# CAN_ISO_Sensor_unit.net
KiCad netlist of a schematic drawn in EAGLE
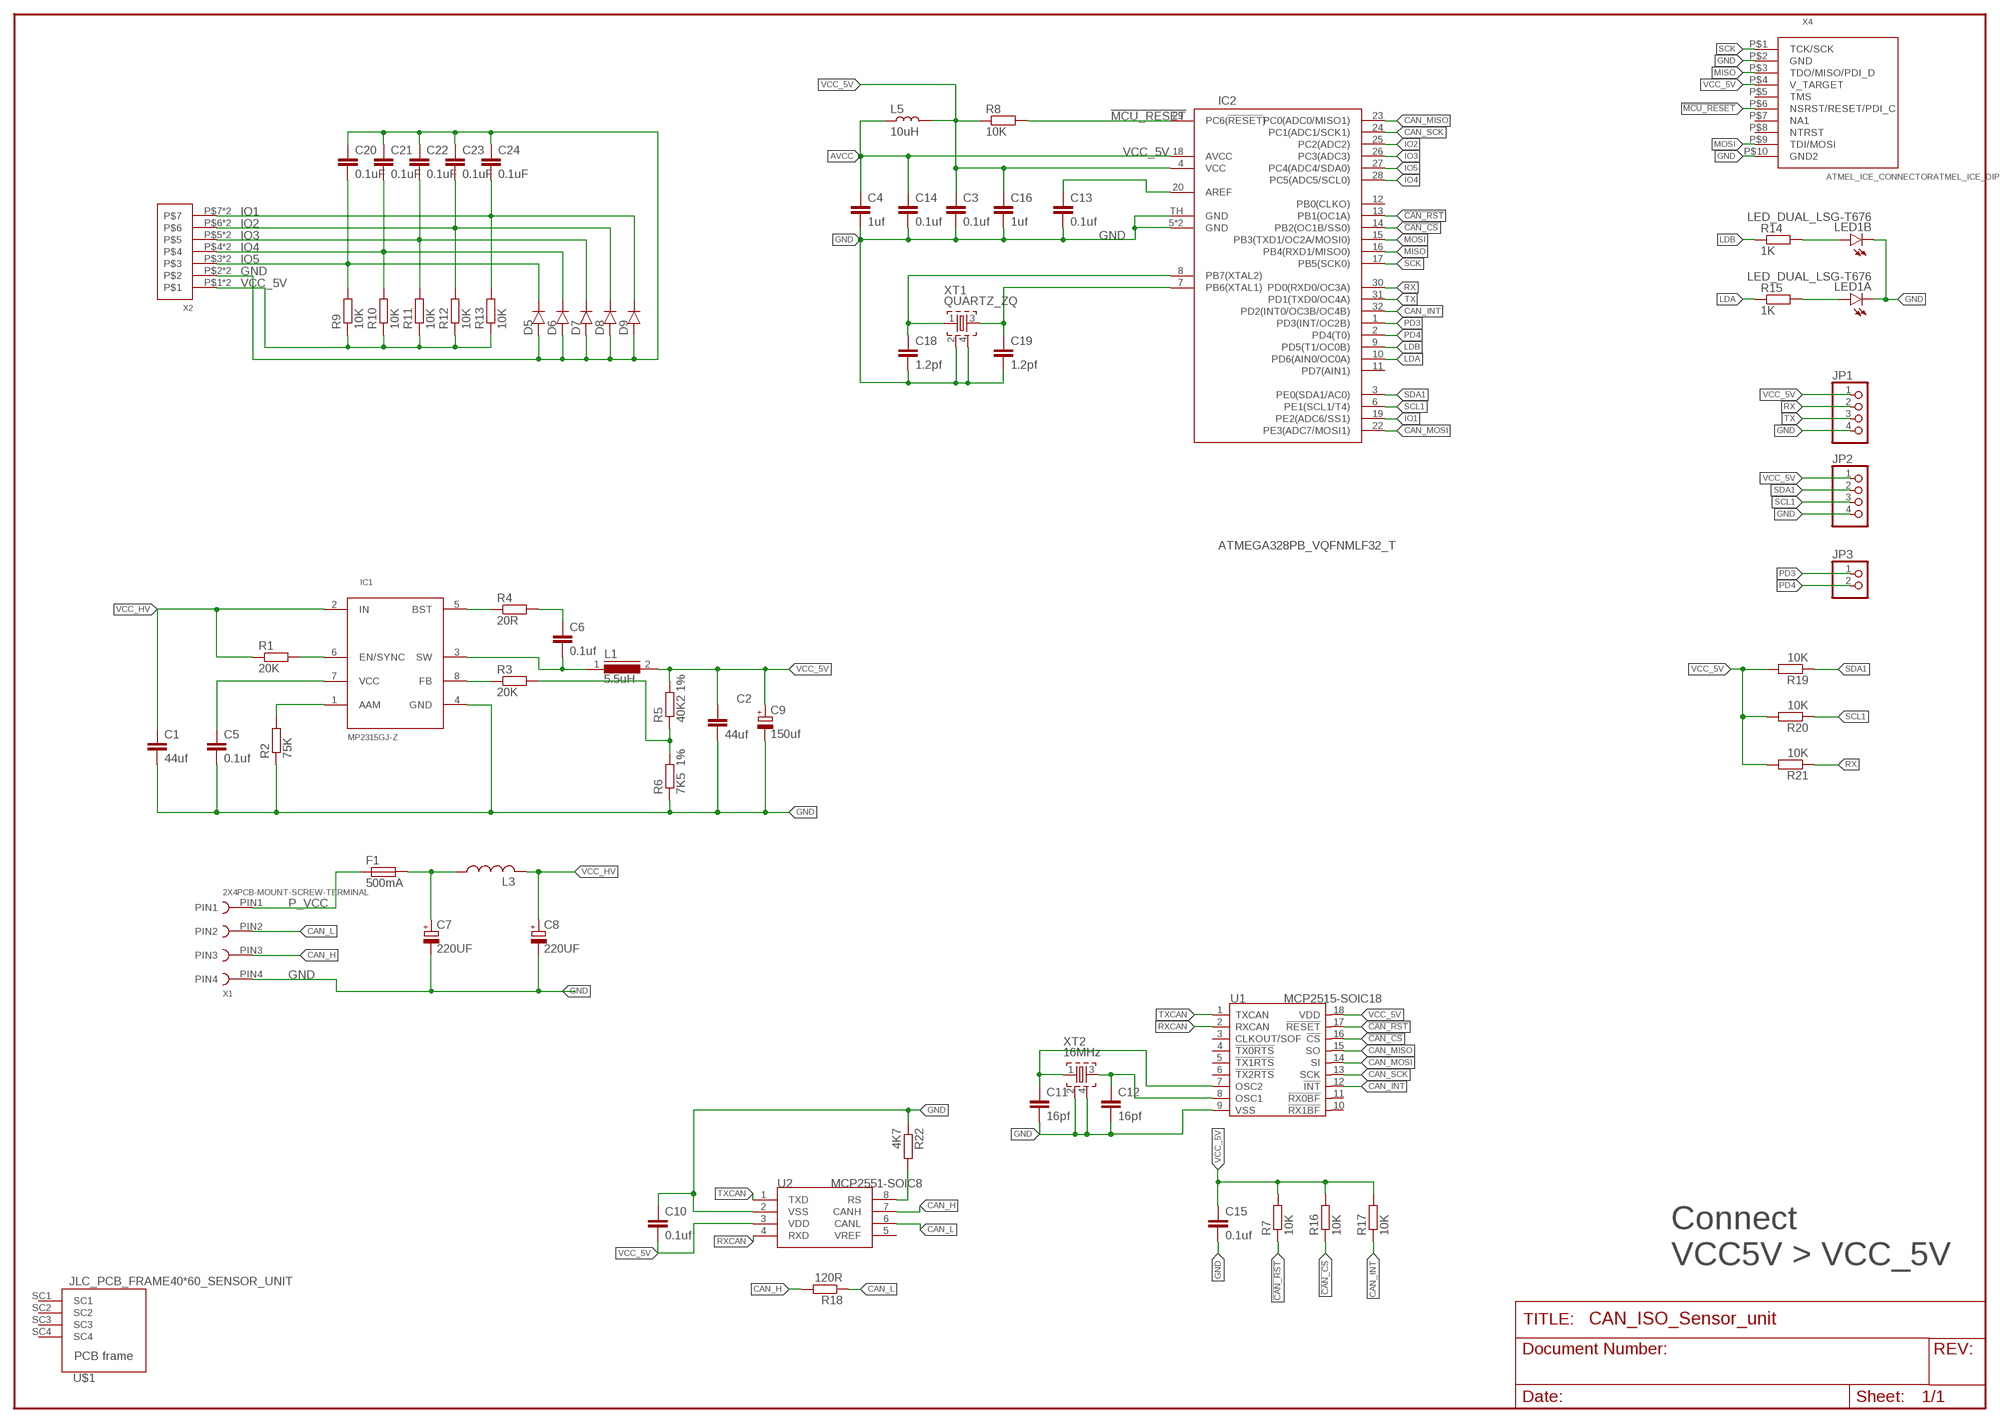
[diagram p0: schematic, sheet 1]

(export (version "E")
  (design (tool "Eeschema 10.0.6"))
  (components
    (comp (ref "C1")
      (value "44uf")
      (footprint "eagle-import:3528_NP")
      (libsource (lib "eagle-import") (part "SMD_C3528"))
    )
    (comp (ref "C2")
      (value "44uf")
      (footprint "eagle-import:3528_NP")
      (libsource (lib "eagle-import") (part "SMD_C3528"))
    )
    (comp (ref "C3")
      (value "0.1uf")
      (footprint "eagle-import:0603")
      (libsource (lib "eagle-import") (part "SMD_C0603"))
    )
    (comp (ref "C4")
      (value "1uf")
      (footprint "eagle-import:0603")
      (libsource (lib "eagle-import") (part "SMD_C0603"))
    )
    (comp (ref "C5")
      (value "0.1uf")
      (footprint "eagle-import:0603")
      (libsource (lib "eagle-import") (part "SMD_C0603"))
    )
    (comp (ref "C6")
      (value "0.1uf")
      (footprint "eagle-import:0603")
      (libsource (lib "eagle-import") (part "SMD_C0603"))
    )
    (comp (ref "C7")
      (value "220UF")
      (footprint "eagle-import:3.6MM")
      (libsource (lib "eagle-import") (part "RADIAL_330UF_25V_8MM"))
    )
    (comp (ref "C8")
      (value "220UF")
      (footprint "eagle-import:3.6MM")
      (libsource (lib "eagle-import") (part "RADIAL_330UF_25V_8MM"))
    )
    (comp (ref "C9")
      (value "150uf")
      (footprint "eagle-import:D_7343-31R")
      (libsource (lib "eagle-import") (part "TANTAL_686_7343"))
    )
    (comp (ref "C10")
      (value "0.1uf")
      (footprint "eagle-import:0603")
      (libsource (lib "eagle-import") (part "SMD_C0603"))
    )
    (comp (ref "C11")
      (value "16pf")
      (footprint "eagle-import:0603")
      (libsource (lib "eagle-import") (part "SMD_C0603"))
    )
    (comp (ref "C12")
      (value "16pf")
      (footprint "eagle-import:0603")
      (libsource (lib "eagle-import") (part "SMD_C0603"))
    )
    (comp (ref "C13")
      (value "0.1uf")
      (footprint "eagle-import:0603")
      (libsource (lib "eagle-import") (part "SMD_C0603"))
    )
    (comp (ref "C14")
      (value "0.1uf")
      (footprint "eagle-import:0603")
      (libsource (lib "eagle-import") (part "SMD_C0603"))
    )
    (comp (ref "C15")
      (value "0.1uf")
      (footprint "eagle-import:0603")
      (libsource (lib "eagle-import") (part "SMD_C0603"))
    )
    (comp (ref "C16")
      (value "1uf")
      (footprint "eagle-import:0603")
      (libsource (lib "eagle-import") (part "SMD_C0603"))
    )
    (comp (ref "C18")
      (value "1.2pf")
      (footprint "eagle-import:0603")
      (libsource (lib "eagle-import") (part "SMD_C0603"))
    )
    (comp (ref "C19")
      (value "1.2pf")
      (footprint "eagle-import:0603")
      (libsource (lib "eagle-import") (part "SMD_C0603"))
    )
    (comp (ref "C20")
      (value "0.1uF")
      (footprint "eagle-import:0603")
      (libsource (lib "eagle-import") (part "SMD_C0603"))
    )
    (comp (ref "C21")
      (value "0.1uF")
      (footprint "eagle-import:0603")
      (libsource (lib "eagle-import") (part "SMD_C0603"))
    )
    (comp (ref "C22")
      (value "0.1uF")
      (footprint "eagle-import:0603")
      (libsource (lib "eagle-import") (part "SMD_C0603"))
    )
    (comp (ref "C23")
      (value "0.1uF")
      (footprint "eagle-import:0603")
      (libsource (lib "eagle-import") (part "SMD_C0603"))
    )
    (comp (ref "C24")
      (value "0.1uF")
      (footprint "eagle-import:0603")
      (libsource (lib "eagle-import") (part "SMD_C0603"))
    )
    (comp (ref "D5")
      (value "L1N4148WT1GSOD123_GALILE0_SMALL")
      (footprint "eagle-import:SOD-123_MINI-SMA")
      (libsource (lib "eagle-import") (part "L1N4148WT1GSOD123_GALILE0_SMALL"))
    )
    (comp (ref "D6")
      (value "L1N4148WT1GSOD123_GALILE0_SMALL")
      (footprint "eagle-import:SOD-123_MINI-SMA")
      (libsource (lib "eagle-import") (part "L1N4148WT1GSOD123_GALILE0_SMALL"))
    )
    (comp (ref "D7")
      (value "L1N4148WT1GSOD123_GALILE0_SMALL")
      (footprint "eagle-import:SOD-123_MINI-SMA")
      (libsource (lib "eagle-import") (part "L1N4148WT1GSOD123_GALILE0_SMALL"))
    )
    (comp (ref "D8")
      (value "L1N4148WT1GSOD123_GALILE0_SMALL")
      (footprint "eagle-import:SOD-123_MINI-SMA")
      (libsource (lib "eagle-import") (part "L1N4148WT1GSOD123_GALILE0_SMALL"))
    )
    (comp (ref "D9")
      (value "L1N4148WT1GSOD123_GALILE0_SMALL")
      (footprint "eagle-import:SOD-123_MINI-SMA")
      (libsource (lib "eagle-import") (part "L1N4148WT1GSOD123_GALILE0_SMALL"))
    )
    (comp (ref "F1")
      (value "500mA")
      (footprint "eagle-import:SMD_2410_FUSE_NOK")
      (libsource (lib "eagle-import") (part "SMD_FUSE"))
    )
    (comp (ref "IC1")
      (value "MP2315GJ-Z")
      (footprint "eagle-import:TSOT23-8")
      (libsource (lib "eagle-import") (part "MP2315GJ-Z"))
    )
    (comp (ref "IC2")
      (value "ATMEGA328PB_VQFNMLF32_T")
      (footprint "eagle-import:MLF32-TH")
      (libsource (lib "eagle-import") (part "ATMEGA328PB_VQFNMLF32_T"))
    )
    (comp (ref "JP1")
      (value "PINHD-1X4")
      (footprint "eagle-import:1X04")
      (libsource (lib "eagle-import") (part "PINHD-1X4"))
    )
    (comp (ref "JP2")
      (value "PINHD-1X4")
      (footprint "eagle-import:1X04")
      (libsource (lib "eagle-import") (part "PINHD-1X4"))
    )
    (comp (ref "JP3")
      (value "PINHD-1X2")
      (footprint "eagle-import:1X02")
      (libsource (lib "eagle-import") (part "PINHD-1X2"))
    )
    (comp (ref "L1")
      (value "5.5uH")
      (footprint "eagle-import:DR73")
      (libsource (lib "eagle-import") (part "DR73"))
    )
    (comp (ref "L3")
      (value "L-US0207/2V")
      (footprint "eagle-import:0207_2V")
      (libsource (lib "eagle-import") (part "L-US0207/2V"))
    )
    (comp (ref "L5")
      (value "10uH")
      (footprint "eagle-import:0805")
      (libsource (lib "eagle-import") (part "SMD_L"))
    )
    (comp (ref "LED1")
      (value "LED_DUAL_LSG-T676")
      (footprint "eagle-import:P-LCC4-0")
      (libsource (lib "eagle-import") (part "LED_DUAL_LSG-T676"))
    )
    (comp (ref "R1")
      (value "20K")
      (footprint "eagle-import:0603")
      (libsource (lib "eagle-import") (part "SMD_R0603"))
    )
    (comp (ref "R2")
      (value "75K")
      (footprint "eagle-import:0603")
      (libsource (lib "eagle-import") (part "SMD_R0603"))
    )
    (comp (ref "R3")
      (value "20K")
      (footprint "eagle-import:0603")
      (libsource (lib "eagle-import") (part "SMD_R0603"))
    )
    (comp (ref "R4")
      (value "20R")
      (footprint "eagle-import:0603")
      (libsource (lib "eagle-import") (part "SMD_R0603"))
    )
    (comp (ref "R5")
      (value "40K2 1%")
      (footprint "eagle-import:0603")
      (libsource (lib "eagle-import") (part "SMD_R0603"))
    )
    (comp (ref "R6")
      (value "7K5 1%")
      (footprint "eagle-import:0603")
      (libsource (lib "eagle-import") (part "SMD_R0603"))
    )
    (comp (ref "R7")
      (value "10K")
      (footprint "eagle-import:0603")
      (libsource (lib "eagle-import") (part "SMD_R0603"))
    )
    (comp (ref "R8")
      (value "10K")
      (footprint "eagle-import:0603")
      (libsource (lib "eagle-import") (part "SMD_R0603"))
    )
    (comp (ref "R9")
      (value "10K")
      (footprint "eagle-import:0603")
      (libsource (lib "eagle-import") (part "SMD_R0603"))
    )
    (comp (ref "R10")
      (value "10K")
      (footprint "eagle-import:0603")
      (libsource (lib "eagle-import") (part "SMD_R0603"))
    )
    (comp (ref "R11")
      (value "10K")
      (footprint "eagle-import:0603")
      (libsource (lib "eagle-import") (part "SMD_R0603"))
    )
    (comp (ref "R12")
      (value "10K")
      (footprint "eagle-import:0603")
      (libsource (lib "eagle-import") (part "SMD_R0603"))
    )
    (comp (ref "R13")
      (value "10K")
      (footprint "eagle-import:0603")
      (libsource (lib "eagle-import") (part "SMD_R0603"))
    )
    (comp (ref "R14")
      (value "1K")
      (footprint "eagle-import:0603")
      (libsource (lib "eagle-import") (part "SMD_R0603"))
    )
    (comp (ref "R15")
      (value "1K")
      (footprint "eagle-import:0603")
      (libsource (lib "eagle-import") (part "SMD_R0603"))
    )
    (comp (ref "R16")
      (value "10K")
      (footprint "eagle-import:0603")
      (libsource (lib "eagle-import") (part "SMD_R0603"))
    )
    (comp (ref "R17")
      (value "10K")
      (footprint "eagle-import:0603")
      (libsource (lib "eagle-import") (part "SMD_R0603"))
    )
    (comp (ref "R18")
      (value "120R")
      (footprint "eagle-import:0603")
      (libsource (lib "eagle-import") (part "SMD_R0603"))
    )
    (comp (ref "R19")
      (value "10K")
      (footprint "eagle-import:0603")
      (libsource (lib "eagle-import") (part "SMD_R0603"))
    )
    (comp (ref "R20")
      (value "10K")
      (footprint "eagle-import:0603")
      (libsource (lib "eagle-import") (part "SMD_R0603"))
    )
    (comp (ref "R21")
      (value "10K")
      (footprint "eagle-import:0603")
      (libsource (lib "eagle-import") (part "SMD_R0603"))
    )
    (comp (ref "R22")
      (value "4K7")
      (footprint "eagle-import:0603")
      (libsource (lib "eagle-import") (part "SMD_R0603"))
    )
    (comp (ref "U$1")
      (value "JLC_PCB_FRAME40*60_SENSOR_UNIT")
      (footprint "eagle-import:40X60_SENSOR_UNIT")
      (libsource (lib "eagle-import") (part "JLC_PCB_FRAME4060_SENSOR_UNIT"))
    )
    (comp (ref "U1")
      (value "MCP2515-SOIC18")
      (footprint "eagle-import:SO18L")
      (libsource (lib "eagle-import") (part "MCP2515-SOIC18"))
    )
    (comp (ref "U2")
      (value "MCP2551-SOIC8")
      (footprint "eagle-import:SO8")
      (libsource (lib "eagle-import") (part "MCP2551-SOIC8"))
    )
    (comp (ref "X1")
      (value "2X4PCB-MOUNT-SCREW-TERMINAL")
      (footprint "eagle-import:2X4PCB-MOUNT-SCREW-TERMINAL")
      (libsource (lib "eagle-import") (part "2X4PCB-MOUNT-SCREW-TERMINAL"))
    )
    (comp (ref "X2")
      (value "WAGO250_X7")
      (footprint "eagle-import:WAGO250_FP_7X")
      (libsource (lib "eagle-import") (part "WAGO250_X7"))
    )
    (comp (ref "X4")
      (value "ATMEL_ICE_CONNECTORATMEL_ICE_DIP_V")
      (footprint "eagle-import:MINI10P_SPI_JTAG_PDI_DIP_V")
      (libsource (lib "eagle-import") (part "ATMEL_ICE_CONNECTORATMEL_ICE_DIP_V"))
    )
    (comp (ref "XT1")
      (value "QUARTZ_ZQ")
      (footprint "eagle-import:QUARTZ_3X3MM")
      (libsource (lib "eagle-import") (part "QUARTZ_ZQ"))
    )
    (comp (ref "XT2")
      (value "16MHz")
      (footprint "eagle-import:QUARTZ_3X3MM")
      (libsource (lib "eagle-import") (part "QUARTZ_ZQ"))
    )
  )
  (nets
    (net (code "1") (name "/P_VCC") (class "Default")
      (node (ref "F1") (pin "P$1") (pinfunction "1_P$1") (pintype "passive"))
      (node (ref "X1") (pin "PIN1") (pinfunction "PIN1_PIN1") (pintype "bidirectional"))
    )
    (net (code "2") (name "/~{CAN_CS}") (class "Default")
      (node (ref "IC2") (pin "14") (pinfunction "PB2(OC1B/SS0)_14") (pintype "bidirectional"))
      (node (ref "R16") (pin "1") (pinfunction "1_1") (pintype "passive"))
      (node (ref "U1") (pin "16") (pinfunction "~{CS}_16") (pintype "input"))
    )
    (net (code "3") (name "/~{CAN_RST}") (class "Default")
      (node (ref "IC2") (pin "13") (pinfunction "PB1(OC1A)_13") (pintype "bidirectional"))
      (node (ref "R7") (pin "1") (pinfunction "1_1") (pintype "passive"))
      (node (ref "U1") (pin "17") (pinfunction "~{RESET}_17") (pintype "input"))
    )
    (net (code "4") (name "/~{MCU_RESET}") (class "Default")
      (node (ref "IC2") (pin "29") (pinfunction "PC6(~{RESET})_29") (pintype "bidirectional"))
      (node (ref "R8") (pin "2") (pinfunction "2_2") (pintype "passive"))
      (node (ref "X4") (pin "P$6") (pinfunction "NSRST/RESET/PDI_C_P$6") (pintype "bidirectional"))
    )
    (net (code "5") (name "AVCC") (class "Default")
      (node (ref "C14") (pin "1") (pinfunction "1_1") (pintype "passive"))
      (node (ref "C4") (pin "1") (pinfunction "1_1") (pintype "passive"))
      (node (ref "IC2") (pin "18") (pinfunction "AVCC_18") (pintype "power_in"))
      (node (ref "L5") (pin "1") (pinfunction "1_1") (pintype "passive"))
    )
    (net (code "6") (name "CAN_H") (class "Default")
      (node (ref "R18") (pin "2") (pinfunction "2_2") (pintype "passive"))
      (node (ref "U2") (pin "7") (pinfunction "CANH_7") (pintype "bidirectional"))
      (node (ref "X1") (pin "PIN3") (pinfunction "PIN3_PIN3") (pintype "bidirectional"))
    )
    (net (code "7") (name "CAN_INT") (class "Default")
      (node (ref "IC2") (pin "32") (pinfunction "PD2(INT0/OC3B/OC4B)_32") (pintype "bidirectional"))
      (node (ref "R17") (pin "1") (pinfunction "1_1") (pintype "passive"))
      (node (ref "U1") (pin "12") (pinfunction "~{INT}_12") (pintype "output"))
    )
    (net (code "8") (name "CAN_L") (class "Default")
      (node (ref "R18") (pin "1") (pinfunction "1_1") (pintype "passive"))
      (node (ref "U2") (pin "6") (pinfunction "CANL_6") (pintype "bidirectional"))
      (node (ref "X1") (pin "PIN2") (pinfunction "PIN2_PIN2") (pintype "bidirectional"))
    )
    (net (code "9") (name "CAN_MISO") (class "Default")
      (node (ref "IC2") (pin "23") (pinfunction "PC0(ADC0/MISO1)_23") (pintype "bidirectional"))
      (node (ref "U1") (pin "15") (pinfunction "SO_15") (pintype "output"))
    )
    (net (code "10") (name "CAN_MOSI") (class "Default")
      (node (ref "IC2") (pin "22") (pinfunction "PE3(ADC7/MOSI1)_22") (pintype "bidirectional"))
      (node (ref "U1") (pin "14") (pinfunction "SI_14") (pintype "input"))
    )
    (net (code "11") (name "CAN_SCK") (class "Default")
      (node (ref "IC2") (pin "24") (pinfunction "PC1(ADC1/SCK1)_24") (pintype "bidirectional"))
      (node (ref "U1") (pin "13") (pinfunction "SCK_13") (pintype "input"))
    )
    (net (code "12") (name "GND") (class "Default")
      (node (ref "C1") (pin "P") (pinfunction "2_P") (pintype "passive"))
      (node (ref "C10") (pin "1") (pinfunction "1_1") (pintype "passive"))
      (node (ref "C11") (pin "2") (pinfunction "2_2") (pintype "passive"))
      (node (ref "C12") (pin "2") (pinfunction "2_2") (pintype "passive"))
      (node (ref "C13") (pin "2") (pinfunction "2_2") (pintype "passive"))
      (node (ref "C14") (pin "2") (pinfunction "2_2") (pintype "passive"))
      (node (ref "C15") (pin "2") (pinfunction "2_2") (pintype "passive"))
      (node (ref "C16") (pin "2") (pinfunction "2_2") (pintype "passive"))
      (node (ref "C18") (pin "2") (pinfunction "2_2") (pintype "passive"))
      (node (ref "C19") (pin "2") (pinfunction "2_2") (pintype "passive"))
      (node (ref "C2") (pin "P") (pinfunction "2_P") (pintype "passive"))
      (node (ref "C20") (pin "1") (pinfunction "1_1") (pintype "passive"))
      (node (ref "C21") (pin "1") (pinfunction "1_1") (pintype "passive"))
      (node (ref "C22") (pin "1") (pinfunction "1_1") (pintype "passive"))
      (node (ref "C23") (pin "1") (pinfunction "1_1") (pintype "passive"))
      (node (ref "C24") (pin "1") (pinfunction "1_1") (pintype "passive"))
      (node (ref "C3") (pin "2") (pinfunction "2_2") (pintype "passive"))
      (node (ref "C4") (pin "2") (pinfunction "2_2") (pintype "passive"))
      (node (ref "C5") (pin "2") (pinfunction "2_2") (pintype "passive"))
      (node (ref "C7") (pin "P$1") (pinfunction "-_P$1") (pintype "passive"))
      (node (ref "C8") (pin "P$1") (pinfunction "-_P$1") (pintype "passive"))
      (node (ref "C9") (pin "-") (pinfunction "-_-") (pintype "passive"))
      (node (ref "D5") (pin "A") (pinfunction "A_A") (pintype "bidirectional"))
      (node (ref "D6") (pin "A") (pinfunction "A_A") (pintype "bidirectional"))
      (node (ref "D7") (pin "A") (pinfunction "A_A") (pintype "bidirectional"))
      (node (ref "D8") (pin "A") (pinfunction "A_A") (pintype "bidirectional"))
      (node (ref "D9") (pin "A") (pinfunction "A_A") (pintype "bidirectional"))
      (node (ref "IC1") (pin "4") (pinfunction "GND_4") (pintype "bidirectional"))
      (node (ref "IC2") (pin "21") (pinfunction "GND_21") (pintype "power_in"))
      (node (ref "IC2") (pin "5") (pinfunction "GND_5") (pintype "power_in"))
      (node (ref "IC2") (pin "TH") (pinfunction "GND_TH") (pintype "power_in"))
      (node (ref "JP1") (pin "4") (pinfunction "4_4") (pintype "passive"))
      (node (ref "JP2") (pin "4") (pinfunction "4_4") (pintype "passive"))
      (node (ref "LED1") (pin "1") (pinfunction "C_1") (pintype "passive"))
      (node (ref "LED1") (pin "3") (pinfunction "C_3") (pintype "passive"))
      (node (ref "R2") (pin "1") (pinfunction "1_1") (pintype "passive"))
      (node (ref "R22") (pin "1") (pinfunction "1_1") (pintype "passive"))
      (node (ref "R6") (pin "1") (pinfunction "1_1") (pintype "passive"))
      (node (ref "U1") (pin "9") (pinfunction "VSS_9") (pintype "power_in"))
      (node (ref "U2") (pin "2") (pinfunction "VSS_2") (pintype "bidirectional"))
      (node (ref "X1") (pin "PIN4") (pinfunction "PIN4_PIN4") (pintype "bidirectional"))
      (node (ref "X2") (pin "P$2") (pinfunction "P$2_P$2") (pintype "bidirectional"))
      (node (ref "X2") (pin "U$2") (pinfunction "P$2_U$2") (pintype "bidirectional"))
      (node (ref "X4") (pin "P$10") (pinfunction "GND2_P$10") (pintype "bidirectional"))
      (node (ref "X4") (pin "P$2") (pinfunction "GND_P$2") (pintype "bidirectional"))
      (node (ref "XT1") (pin "2") (pinfunction "2_2") (pintype "passive"))
      (node (ref "XT1") (pin "4") (pinfunction "4_4") (pintype "passive"))
      (node (ref "XT2") (pin "2") (pinfunction "2_2") (pintype "passive"))
      (node (ref "XT2") (pin "4") (pinfunction "4_4") (pintype "passive"))
    )
    (net (code "13") (name "IO1") (class "Default")
      (node (ref "C24") (pin "2") (pinfunction "2_2") (pintype "passive"))
      (node (ref "D9") (pin "C") (pinfunction "C_C") (pintype "bidirectional"))
      (node (ref "IC2") (pin "19") (pinfunction "PE2(ADC6/SS1)_19") (pintype "bidirectional"))
      (node (ref "R13") (pin "2") (pinfunction "2_2") (pintype "passive"))
      (node (ref "X2") (pin "P$7") (pinfunction "P$7_P$7") (pintype "bidirectional"))
      (node (ref "X2") (pin "U$7") (pinfunction "P$7_U$7") (pintype "bidirectional"))
    )
    (net (code "14") (name "IO2") (class "Default")
      (node (ref "C23") (pin "2") (pinfunction "2_2") (pintype "passive"))
      (node (ref "D8") (pin "C") (pinfunction "C_C") (pintype "bidirectional"))
      (node (ref "IC2") (pin "25") (pinfunction "PC2(ADC2)_25") (pintype "bidirectional"))
      (node (ref "R12") (pin "2") (pinfunction "2_2") (pintype "passive"))
      (node (ref "X2") (pin "P$6") (pinfunction "P$6_P$6") (pintype "bidirectional"))
      (node (ref "X2") (pin "U$6") (pinfunction "P$6_U$6") (pintype "bidirectional"))
    )
    (net (code "15") (name "IO3") (class "Default")
      (node (ref "C22") (pin "2") (pinfunction "2_2") (pintype "passive"))
      (node (ref "D7") (pin "C") (pinfunction "C_C") (pintype "bidirectional"))
      (node (ref "IC2") (pin "26") (pinfunction "PC3(ADC3)_26") (pintype "bidirectional"))
      (node (ref "R11") (pin "2") (pinfunction "2_2") (pintype "passive"))
      (node (ref "X2") (pin "P$5") (pinfunction "P$5_P$5") (pintype "bidirectional"))
      (node (ref "X2") (pin "U$5") (pinfunction "P$5_U$5") (pintype "bidirectional"))
    )
    (net (code "16") (name "IO4") (class "Default")
      (node (ref "C21") (pin "2") (pinfunction "2_2") (pintype "passive"))
      (node (ref "D6") (pin "C") (pinfunction "C_C") (pintype "bidirectional"))
      (node (ref "IC2") (pin "28") (pinfunction "PC5(ADC5/SCL0)_28") (pintype "bidirectional"))
      (node (ref "R10") (pin "2") (pinfunction "2_2") (pintype "passive"))
      (node (ref "X2") (pin "P$4") (pinfunction "P$4_P$4") (pintype "bidirectional"))
      (node (ref "X2") (pin "U$4") (pinfunction "P$4_U$4") (pintype "bidirectional"))
    )
    (net (code "17") (name "IO5") (class "Default")
      (node (ref "C20") (pin "2") (pinfunction "2_2") (pintype "passive"))
      (node (ref "D5") (pin "C") (pinfunction "C_C") (pintype "bidirectional"))
      (node (ref "IC2") (pin "27") (pinfunction "PC4(ADC4/SDA0)_27") (pintype "bidirectional"))
      (node (ref "R9") (pin "2") (pinfunction "2_2") (pintype "passive"))
      (node (ref "X2") (pin "P$3") (pinfunction "P$3_P$3") (pintype "bidirectional"))
      (node (ref "X2") (pin "U$3") (pinfunction "P$3_U$3") (pintype "bidirectional"))
    )
    (net (code "18") (name "LDA") (class "Default")
      (node (ref "IC2") (pin "10") (pinfunction "PD6(AIN0/OC0A)_10") (pintype "bidirectional"))
      (node (ref "R15") (pin "1") (pinfunction "1_1") (pintype "passive"))
    )
    (net (code "19") (name "LDB") (class "Default")
      (node (ref "IC2") (pin "9") (pinfunction "PD5(T1/OC0B)_9") (pintype "bidirectional"))
      (node (ref "R14") (pin "1") (pinfunction "1_1") (pintype "passive"))
    )
    (net (code "20") (name "MISO") (class "Default")
      (node (ref "IC2") (pin "16") (pinfunction "PB4(RXD1/MISO0)_16") (pintype "bidirectional"))
      (node (ref "X4") (pin "P$3") (pinfunction "TDO/MISO/PDI_D_P$3") (pintype "bidirectional"))
    )
    (net (code "21") (name "MOSI") (class "Default")
      (node (ref "IC2") (pin "15") (pinfunction "PB3(TXD1/OC2A/MOSI0)_15") (pintype "bidirectional"))
      (node (ref "X4") (pin "P$9") (pinfunction "TDI/MOSI_P$9") (pintype "bidirectional"))
    )
    (net (code "22") (name "Net-(C6-Pad1)") (class "Default")
      (node (ref "C6") (pin "1") (pinfunction "1_1") (pintype "passive"))
      (node (ref "R4") (pin "2") (pinfunction "2_2") (pintype "passive"))
    )
    (net (code "23") (name "Net-(C7-+)") (class "Default")
      (node (ref "C7") (pin "P$2") (pinfunction "+_P$2") (pintype "passive"))
      (node (ref "F1") (pin "P$2") (pinfunction "2_P$2") (pintype "passive"))
      (node (ref "L3") (pin "1") (pinfunction "1_1") (pintype "passive"))
    )
    (net (code "24") (name "Net-(IC1-AAM)") (class "Default")
      (node (ref "IC1") (pin "1") (pinfunction "AAM_1") (pintype "bidirectional"))
      (node (ref "R2") (pin "2") (pinfunction "2_2") (pintype "passive"))
    )
    (net (code "25") (name "Net-(IC1-BST)") (class "Default")
      (node (ref "IC1") (pin "5") (pinfunction "BST_5") (pintype "bidirectional"))
      (node (ref "R4") (pin "1") (pinfunction "1_1") (pintype "passive"))
    )
    (net (code "26") (name "Net-(IC1-EN{slash}SYNC)") (class "Default")
      (node (ref "IC1") (pin "6") (pinfunction "EN/SYNC_6") (pintype "bidirectional"))
      (node (ref "R1") (pin "2") (pinfunction "2_2") (pintype "passive"))
    )
    (net (code "27") (name "Net-(IC1-FB)") (class "Default")
      (node (ref "IC1") (pin "8") (pinfunction "FB_8") (pintype "bidirectional"))
      (node (ref "R3") (pin "1") (pinfunction "1_1") (pintype "passive"))
    )
    (net (code "28") (name "Net-(IC1-SW)") (class "Default")
      (node (ref "C6") (pin "2") (pinfunction "2_2") (pintype "passive"))
      (node (ref "IC1") (pin "3") (pinfunction "SW_3") (pintype "bidirectional"))
      (node (ref "L1") (pin "1") (pinfunction "1_1") (pintype "passive"))
    )
    (net (code "29") (name "Net-(IC1-VCC)") (class "Default")
      (node (ref "C5") (pin "1") (pinfunction "1_1") (pintype "passive"))
      (node (ref "IC1") (pin "7") (pinfunction "VCC_7") (pintype "bidirectional"))
    )
    (net (code "30") (name "Net-(IC2-AREF)") (class "Default")
      (node (ref "C13") (pin "1") (pinfunction "1_1") (pintype "passive"))
      (node (ref "IC2") (pin "20") (pinfunction "AREF_20") (pintype "passive"))
    )
    (net (code "31") (name "Net-(IC2-PB6(XTAL1))") (class "Default")
      (node (ref "C19") (pin "1") (pinfunction "1_1") (pintype "passive"))
      (node (ref "IC2") (pin "7") (pinfunction "PB6(XTAL1)_7") (pintype "bidirectional"))
      (node (ref "XT1") (pin "3") (pinfunction "3_3") (pintype "passive"))
    )
    (net (code "32") (name "Net-(IC2-PB7(XTAL2))") (class "Default")
      (node (ref "C18") (pin "1") (pinfunction "1_1") (pintype "passive"))
      (node (ref "IC2") (pin "8") (pinfunction "PB7(XTAL2)_8") (pintype "bidirectional"))
      (node (ref "XT1") (pin "1") (pinfunction "1_1") (pintype "passive"))
    )
    (net (code "33") (name "Net-(LED1A-A)") (class "Default")
      (node (ref "LED1") (pin "2") (pinfunction "A_2") (pintype "passive"))
      (node (ref "R15") (pin "2") (pinfunction "2_2") (pintype "passive"))
    )
    (net (code "34") (name "Net-(LED1B-A)") (class "Default")
      (node (ref "LED1") (pin "4") (pinfunction "A_4") (pintype "passive"))
      (node (ref "R14") (pin "2") (pinfunction "2_2") (pintype "passive"))
    )
    (net (code "35") (name "Net-(R3-Pad2)") (class "Default")
      (node (ref "R3") (pin "2") (pinfunction "2_2") (pintype "passive"))
      (node (ref "R5") (pin "1") (pinfunction "1_1") (pintype "passive"))
      (node (ref "R6") (pin "2") (pinfunction "2_2") (pintype "passive"))
    )
    (net (code "36") (name "Net-(U1-OSC1)") (class "Default")
      (node (ref "C12") (pin "1") (pinfunction "1_1") (pintype "passive"))
      (node (ref "U1") (pin "8") (pinfunction "OSC1_8") (pintype "input"))
      (node (ref "XT2") (pin "3") (pinfunction "3_3") (pintype "passive"))
    )
    (net (code "37") (name "Net-(U1-OSC2)") (class "Default")
      (node (ref "C11") (pin "1") (pinfunction "1_1") (pintype "passive"))
      (node (ref "U1") (pin "7") (pinfunction "OSC2_7") (pintype "output"))
      (node (ref "XT2") (pin "1") (pinfunction "1_1") (pintype "passive"))
    )
    (net (code "38") (name "Net-(U2-RS)") (class "Default")
      (node (ref "R22") (pin "2") (pinfunction "2_2") (pintype "passive"))
      (node (ref "U2") (pin "8") (pinfunction "RS_8") (pintype "bidirectional"))
    )
    (net (code "39") (name "PD3") (class "Default")
      (node (ref "IC2") (pin "1") (pinfunction "PD3(INT/OC2B)_1") (pintype "bidirectional"))
      (node (ref "JP3") (pin "1") (pinfunction "1_1") (pintype "passive"))
    )
    (net (code "40") (name "PD4") (class "Default")
      (node (ref "IC2") (pin "2") (pinfunction "PD4(T0)_2") (pintype "bidirectional"))
      (node (ref "JP3") (pin "2") (pinfunction "2_2") (pintype "passive"))
    )
    (net (code "41") (name "RX") (class "Default")
      (node (ref "IC2") (pin "30") (pinfunction "PD0(RXD0/OC3A)_30") (pintype "bidirectional"))
      (node (ref "JP1") (pin "2") (pinfunction "2_2") (pintype "passive"))
      (node (ref "R21") (pin "1") (pinfunction "1_1") (pintype "passive"))
    )
    (net (code "42") (name "RXCAN") (class "Default")
      (node (ref "U1") (pin "2") (pinfunction "RXCAN_2") (pintype "input"))
      (node (ref "U2") (pin "4") (pinfunction "RXD_4") (pintype "bidirectional"))
    )
    (net (code "43") (name "SCK") (class "Default")
      (node (ref "IC2") (pin "17") (pinfunction "PB5(SCK0)_17") (pintype "bidirectional"))
      (node (ref "X4") (pin "P$1") (pinfunction "TCK/SCK_P$1") (pintype "bidirectional"))
    )
    (net (code "44") (name "SCL1") (class "Default")
      (node (ref "IC2") (pin "6") (pinfunction "PE1(SCL1/T4)_6") (pintype "bidirectional"))
      (node (ref "JP2") (pin "3") (pinfunction "3_3") (pintype "passive"))
      (node (ref "R20") (pin "1") (pinfunction "1_1") (pintype "passive"))
    )
    (net (code "45") (name "SDA1") (class "Default")
      (node (ref "IC2") (pin "3") (pinfunction "PE0(SDA1/AC0)_3") (pintype "bidirectional"))
      (node (ref "JP2") (pin "2") (pinfunction "2_2") (pintype "passive"))
      (node (ref "R19") (pin "1") (pinfunction "1_1") (pintype "passive"))
    )
    (net (code "46") (name "TX") (class "Default")
      (node (ref "IC2") (pin "31") (pinfunction "PD1(TXD0/OC4A)_31") (pintype "bidirectional"))
      (node (ref "JP1") (pin "3") (pinfunction "3_3") (pintype "passive"))
    )
    (net (code "47") (name "TXCAN") (class "Default")
      (node (ref "U1") (pin "1") (pinfunction "TXCAN_1") (pintype "output"))
      (node (ref "U2") (pin "1") (pinfunction "TXD_1") (pintype "bidirectional"))
    )
    (net (code "48") (name "VCC_5V") (class "Default")
      (node (ref "C10") (pin "2") (pinfunction "2_2") (pintype "passive"))
      (node (ref "C15") (pin "1") (pinfunction "1_1") (pintype "passive"))
      (node (ref "C16") (pin "1") (pinfunction "1_1") (pintype "passive"))
      (node (ref "C2") (pin "M") (pinfunction "1_M") (pintype "passive"))
      (node (ref "C3") (pin "1") (pinfunction "1_1") (pintype "passive"))
      (node (ref "C9") (pin "+") (pinfunction "+_+") (pintype "passive"))
      (node (ref "IC2") (pin "4") (pinfunction "VCC_4") (pintype "power_in"))
      (node (ref "JP1") (pin "1") (pinfunction "1_1") (pintype "passive"))
      (node (ref "JP2") (pin "1") (pinfunction "1_1") (pintype "passive"))
      (node (ref "L1") (pin "2") (pinfunction "2_2") (pintype "passive"))
      (node (ref "L5") (pin "2") (pinfunction "2_2") (pintype "passive"))
      (node (ref "R10") (pin "1") (pinfunction "1_1") (pintype "passive"))
      (node (ref "R11") (pin "1") (pinfunction "1_1") (pintype "passive"))
      (node (ref "R12") (pin "1") (pinfunction "1_1") (pintype "passive"))
      (node (ref "R13") (pin "1") (pinfunction "1_1") (pintype "passive"))
      (node (ref "R16") (pin "2") (pinfunction "2_2") (pintype "passive"))
      (node (ref "R17") (pin "2") (pinfunction "2_2") (pintype "passive"))
      (node (ref "R19") (pin "2") (pinfunction "2_2") (pintype "passive"))
      (node (ref "R20") (pin "2") (pinfunction "2_2") (pintype "passive"))
      (node (ref "R21") (pin "2") (pinfunction "2_2") (pintype "passive"))
      (node (ref "R5") (pin "2") (pinfunction "2_2") (pintype "passive"))
      (node (ref "R7") (pin "2") (pinfunction "2_2") (pintype "passive"))
      (node (ref "R8") (pin "1") (pinfunction "1_1") (pintype "passive"))
      (node (ref "R9") (pin "1") (pinfunction "1_1") (pintype "passive"))
      (node (ref "U1") (pin "18") (pinfunction "VDD_18") (pintype "power_in"))
      (node (ref "U2") (pin "3") (pinfunction "VDD_3") (pintype "bidirectional"))
      (node (ref "X2") (pin "P$1") (pinfunction "P$1_P$1") (pintype "bidirectional"))
      (node (ref "X2") (pin "U$1") (pinfunction "P$1_U$1") (pintype "bidirectional"))
      (node (ref "X4") (pin "P$4") (pinfunction "V_TARGET_P$4") (pintype "bidirectional"))
    )
    (net (code "49") (name "VCC_HV") (class "Default")
      (node (ref "C1") (pin "M") (pinfunction "1_M") (pintype "passive"))
      (node (ref "C8") (pin "P$2") (pinfunction "+_P$2") (pintype "passive"))
      (node (ref "IC1") (pin "2") (pinfunction "IN_2") (pintype "bidirectional"))
      (node (ref "L3") (pin "2") (pinfunction "2_2") (pintype "passive"))
      (node (ref "R1") (pin "1") (pinfunction "1_1") (pintype "passive"))
    )
    (net (code "50") (name "unconnected-(IC2-PB0(CLKO)-Pad12)") (class "Default")
      (node (ref "IC2") (pin "12") (pinfunction "PB0(CLKO)_12") (pintype "bidirectional"))
    )
    (net (code "51") (name "unconnected-(IC2-PD7(AIN1)-Pad11)") (class "Default")
      (node (ref "IC2") (pin "11") (pinfunction "PD7(AIN1)_11") (pintype "bidirectional"))
    )
    (net (code "52") (name "unconnected-(U$1-PadSC1)") (class "Default")
      (node (ref "U$1") (pin "SC1") (pinfunction "SC1_SC1") (pintype "bidirectional"))
    )
    (net (code "53") (name "unconnected-(U$1-PadSC2)") (class "Default")
      (node (ref "U$1") (pin "SC2") (pinfunction "SC2_SC2") (pintype "bidirectional"))
    )
    (net (code "54") (name "unconnected-(U$1-PadSC3)") (class "Default")
      (node (ref "U$1") (pin "SC3") (pinfunction "SC3_SC3") (pintype "bidirectional"))
    )
    (net (code "55") (name "unconnected-(U$1-PadSC4)") (class "Default")
      (node (ref "U$1") (pin "SC4") (pinfunction "SC4_SC4") (pintype "bidirectional"))
    )
    (net (code "56") (name "unconnected-(U1-CLKOUT{slash}SOF-Pad3)") (class "Default")
      (node (ref "U1") (pin "3") (pinfunction "CLKOUT/SOF_3") (pintype "output"))
    )
    (net (code "57") (name "unconnected-(U1-~{RX0BF}-Pad11)") (class "Default")
      (node (ref "U1") (pin "11") (pinfunction "~{RX0BF}_11") (pintype "output"))
    )
    (net (code "58") (name "unconnected-(U1-~{RX1BF}-Pad10)") (class "Default")
      (node (ref "U1") (pin "10") (pinfunction "~{RX1BF}_10") (pintype "output"))
    )
    (net (code "59") (name "unconnected-(U1-~{TX0RTS}-Pad4)") (class "Default")
      (node (ref "U1") (pin "4") (pinfunction "~{TX0RTS}_4") (pintype "input"))
    )
    (net (code "60") (name "unconnected-(U1-~{TX1RTS}-Pad5)") (class "Default")
      (node (ref "U1") (pin "5") (pinfunction "~{TX1RTS}_5") (pintype "input"))
    )
    (net (code "61") (name "unconnected-(U1-~{TX2RTS}-Pad6)") (class "Default")
      (node (ref "U1") (pin "6") (pinfunction "~{TX2RTS}_6") (pintype "input"))
    )
    (net (code "62") (name "unconnected-(U2-VREF-Pad5)") (class "Default")
      (node (ref "U2") (pin "5") (pinfunction "VREF_5") (pintype "bidirectional"))
    )
    (net (code "63") (name "unconnected-(X4-NA1-PadP$7)") (class "Default")
      (node (ref "X4") (pin "P$7") (pinfunction "NA1_P$7") (pintype "bidirectional"))
    )
    (net (code "64") (name "unconnected-(X4-NTRST-PadP$8)") (class "Default")
      (node (ref "X4") (pin "P$8") (pinfunction "NTRST_P$8") (pintype "bidirectional"))
    )
    (net (code "65") (name "unconnected-(X4-TMS-PadP$5)") (class "Default")
      (node (ref "X4") (pin "P$5") (pinfunction "TMS_P$5") (pintype "bidirectional"))
    )
  )
)
